# PA.net
KiCad netlist of a schematic drawn in EAGLE
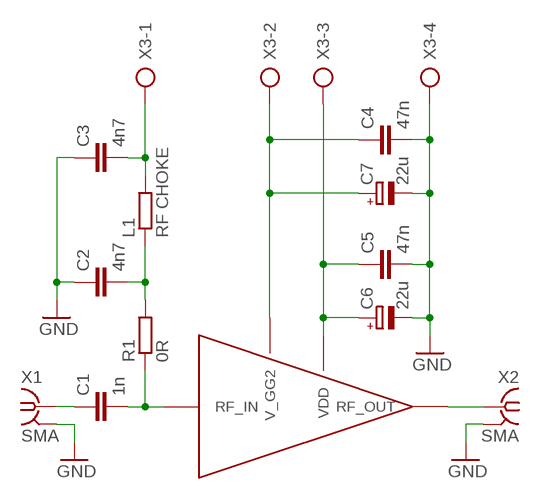
[diagram p0: schematic, sheet 1]

(export (version "E")
  (design (tool "Eeschema 10.0.6"))
  (components
    (comp (ref "C1")
      (value "1n")
      (footprint "eagle-import:C0805K")
      (libsource (lib "eagle-import") (part "C-EUC0805K"))
    )
    (comp (ref "C2")
      (value "4n7")
      (footprint "eagle-import:C0805K")
      (libsource (lib "eagle-import") (part "C-EUC0805K"))
    )
    (comp (ref "C3")
      (value "4n7")
      (footprint "eagle-import:C0805K")
      (libsource (lib "eagle-import") (part "C-EUC0805K"))
    )
    (comp (ref "C4")
      (value "47n")
      (footprint "eagle-import:C1206K")
      (libsource (lib "eagle-import") (part "C-EUC1206K"))
    )
    (comp (ref "C5")
      (value "47n")
      (footprint "eagle-import:C1206K")
      (libsource (lib "eagle-import") (part "C-EUC1206K"))
    )
    (comp (ref "C6")
      (value "22u")
      (footprint "eagle-import:153CLV-1010")
      (libsource (lib "eagle-import") (part "CPOL-EU153CLV-1010"))
    )
    (comp (ref "C7")
      (value "22u")
      (footprint "eagle-import:153CLV-1010")
      (libsource (lib "eagle-import") (part "CPOL-EU153CLV-1010"))
    )
    (comp (ref "L1")
      (value "RF CHOKE")
      (footprint "eagle-import:R0805")
      (libsource (lib "eagle-import") (part "R-EU_R0805"))
    )
    (comp (ref "R1")
      (value "0R")
      (footprint "eagle-import:R0805")
      (libsource (lib "eagle-import") (part "R-EU_R0805"))
    )
    (comp (ref "U$1")
      (value "RA45H8994M1")
      (footprint "eagle-import:RF_MODULE")
      (libsource (lib "eagle-import") (part "RA45H8994M1"))
    )
    (comp (ref "X1")
      (value "SMA")
      (footprint "eagle-import:J502-ND-142-0701-801_806")
      (fields (field (name "MF") "JOHNSON COMPONENTS") (field (name "MPN") "142-0701-801"))
      (libsource (lib "eagle-import") (part "SMA-142-0701-801/806"))
    )
    (comp (ref "X2")
      (value "SMA")
      (footprint "eagle-import:J502-ND-142-0701-801_806")
      (fields (field (name "MF") "JOHNSON COMPONENTS") (field (name "MPN") "142-0701-801"))
      (libsource (lib "eagle-import") (part "SMA-142-0701-801/806"))
    )
    (comp (ref "X3")
      (value "AK500/4")
      (footprint "eagle-import:AK500_4")
      (libsource (lib "eagle-import") (part "AK500/4"))
    )
  )
  (nets
    (net (code "1") (name "GND") (class "Default")
      (node (ref "C2") (pin "1") (pinfunction "1_1") (pintype "passive"))
      (node (ref "C3") (pin "1") (pinfunction "1_1") (pintype "passive"))
      (node (ref "C4") (pin "2") (pinfunction "2_2") (pintype "passive"))
      (node (ref "C5") (pin "2") (pinfunction "2_2") (pintype "passive"))
      (node (ref "C6") (pin "-") (pinfunction "-_-") (pintype "passive"))
      (node (ref "C7") (pin "-") (pinfunction "-_-") (pintype "passive"))
      (node (ref "X1") (pin "G@1") (pinfunction "2_G@1") (pintype "passive"))
      (node (ref "X1") (pin "G@2") (pinfunction "2_G@2") (pintype "passive"))
      (node (ref "X1") (pin "G@3") (pinfunction "2_G@3") (pintype "passive"))
      (node (ref "X1") (pin "G@4") (pinfunction "2_G@4") (pintype "passive"))
      (node (ref "X2") (pin "G@1") (pinfunction "2_G@1") (pintype "passive"))
      (node (ref "X2") (pin "G@2") (pinfunction "2_G@2") (pintype "passive"))
      (node (ref "X2") (pin "G@3") (pinfunction "2_G@3") (pintype "passive"))
      (node (ref "X2") (pin "G@4") (pinfunction "2_G@4") (pintype "passive"))
      (node (ref "X3") (pin "4") (pinfunction "KL_4") (pintype "passive"))
    )
    (net (code "2") (name "Net-(C1-Pad1)") (class "Default")
      (node (ref "C1") (pin "1") (pinfunction "1_1") (pintype "passive"))
      (node (ref "X1") (pin "1") (pinfunction "1_1") (pintype "passive"))
    )
    (net (code "3") (name "Net-(C1-Pad2)") (class "Default")
      (node (ref "C1") (pin "2") (pinfunction "2_2") (pintype "passive"))
      (node (ref "R1") (pin "1") (pinfunction "1_1") (pintype "passive"))
      (node (ref "U$1") (pin "RF_IN") (pinfunction "RF_IN_RF_IN") (pintype "input"))
    )
    (net (code "4") (name "Net-(C2-Pad2)") (class "Default")
      (node (ref "C2") (pin "2") (pinfunction "2_2") (pintype "passive"))
      (node (ref "L1") (pin "1") (pinfunction "1_1") (pintype "passive"))
      (node (ref "R1") (pin "2") (pinfunction "2_2") (pintype "passive"))
    )
    (net (code "5") (name "Net-(U$1-PadRF_OUT)") (class "Default")
      (node (ref "U$1") (pin "RF_OUT") (pinfunction "RF_OUT_RF_OUT") (pintype "output"))
      (node (ref "X2") (pin "1") (pinfunction "1_1") (pintype "passive"))
    )
    (net (code "6") (name "Net-(X3A-KL)") (class "Default")
      (node (ref "C3") (pin "2") (pinfunction "2_2") (pintype "passive"))
      (node (ref "L1") (pin "2") (pinfunction "2_2") (pintype "passive"))
      (node (ref "X3") (pin "1") (pinfunction "KL_1") (pintype "passive"))
    )
    (net (code "7") (name "Net-(X3B-KL)") (class "Default")
      (node (ref "C4") (pin "1") (pinfunction "1_1") (pintype "passive"))
      (node (ref "C7") (pin "+") (pinfunction "+_+") (pintype "passive"))
      (node (ref "U$1") (pin "V_GG2") (pinfunction "V_GG2_V_GG2") (pintype "power_in"))
      (node (ref "X3") (pin "2") (pinfunction "KL_2") (pintype "passive"))
    )
    (net (code "8") (name "Net-(X3C-KL)") (class "Default")
      (node (ref "C5") (pin "1") (pinfunction "1_1") (pintype "passive"))
      (node (ref "C6") (pin "+") (pinfunction "+_+") (pintype "passive"))
      (node (ref "U$1") (pin "VDD") (pinfunction "VDD_VDD") (pintype "power_in"))
      (node (ref "X3") (pin "3") (pinfunction "KL_3") (pintype "passive"))
    )
  )
)
